# Power_systems_board_REV2.net
KiCad netlist of a schematic drawn in EAGLE
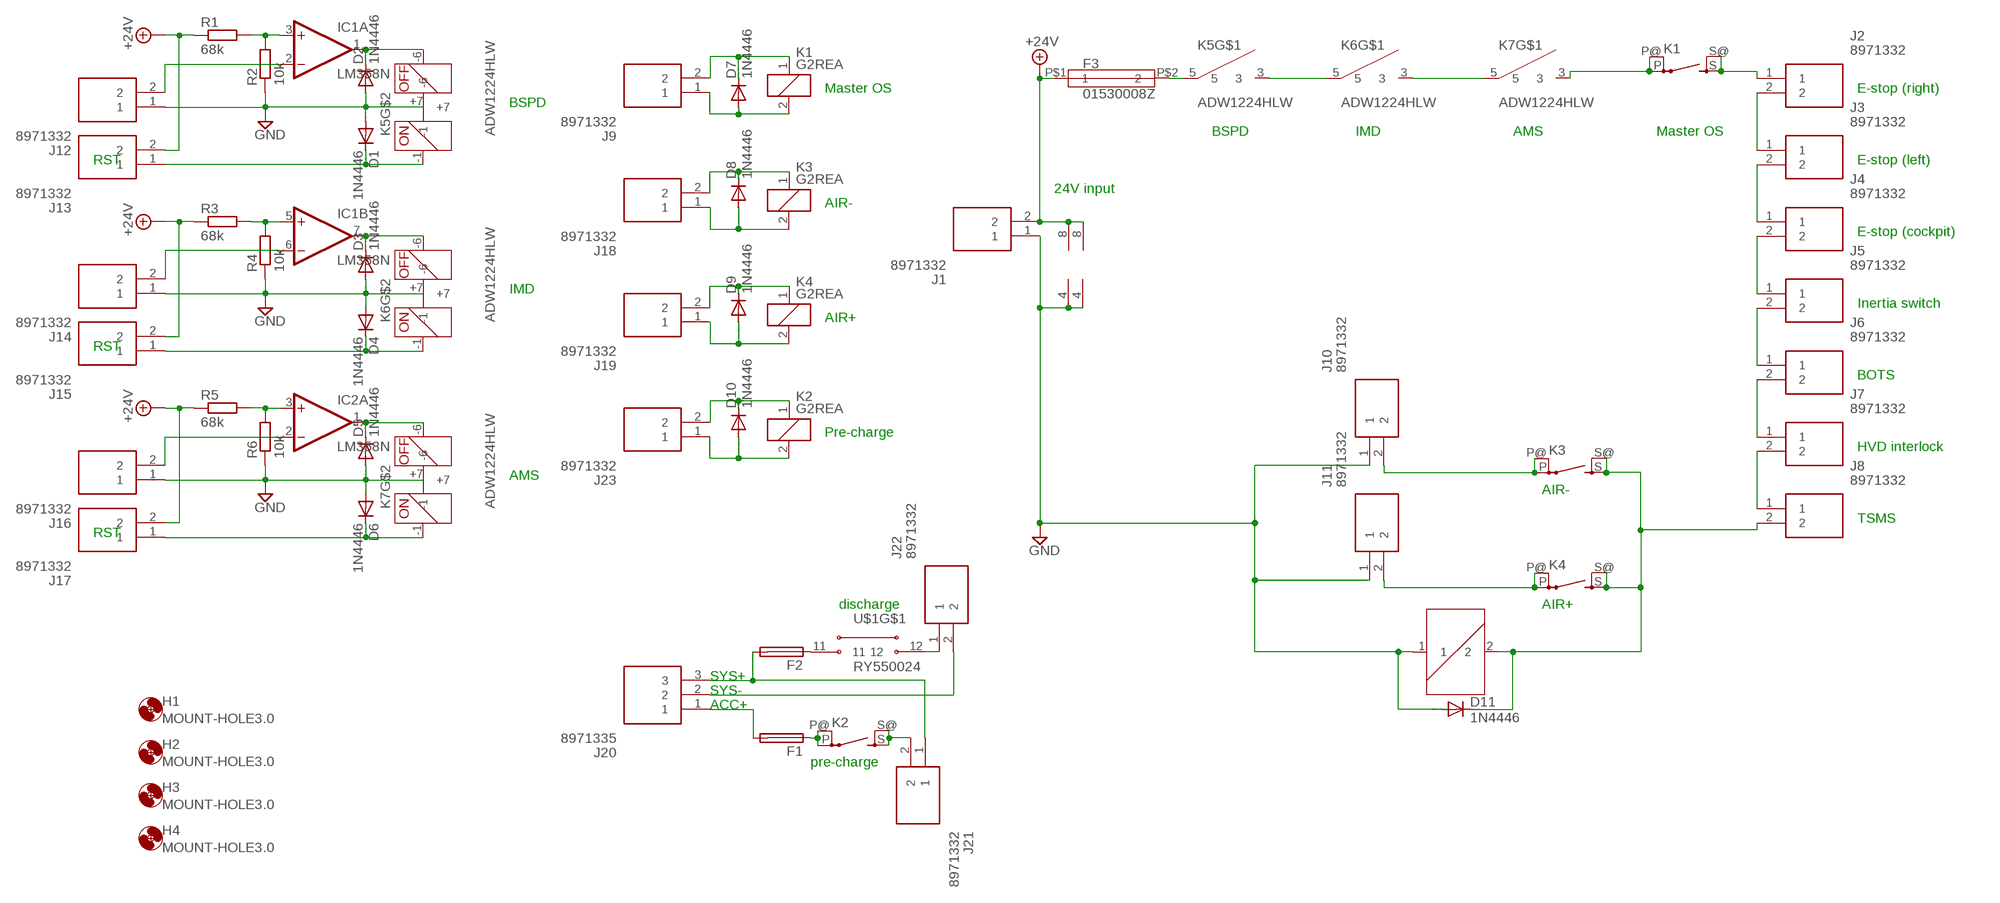
[diagram p0: schematic, sheet 1]

(export (version "E")
  (design (tool "Eeschema 10.0.6"))
  (components
    (comp (ref "D1")
      (value "1N4446")
      (footprint "eagle-import:DO35-10")
      (libsource (lib "eagle-import") (part "1N4446"))
    )
    (comp (ref "D2")
      (value "1N4446")
      (footprint "eagle-import:DO35-10")
      (libsource (lib "eagle-import") (part "1N4446"))
    )
    (comp (ref "D3")
      (value "1N4446")
      (footprint "eagle-import:DO35-10")
      (libsource (lib "eagle-import") (part "1N4446"))
    )
    (comp (ref "D4")
      (value "1N4446")
      (footprint "eagle-import:DO35-10")
      (libsource (lib "eagle-import") (part "1N4446"))
    )
    (comp (ref "D5")
      (value "1N4446")
      (footprint "eagle-import:DO35-10")
      (libsource (lib "eagle-import") (part "1N4446"))
    )
    (comp (ref "D6")
      (value "1N4446")
      (footprint "eagle-import:DO35-10")
      (libsource (lib "eagle-import") (part "1N4446"))
    )
    (comp (ref "D7")
      (value "1N4446")
      (footprint "eagle-import:DO35-10")
      (libsource (lib "eagle-import") (part "1N4446"))
    )
    (comp (ref "D8")
      (value "1N4446")
      (footprint "eagle-import:DO35-10")
      (libsource (lib "eagle-import") (part "1N4446"))
    )
    (comp (ref "D9")
      (value "1N4446")
      (footprint "eagle-import:DO35-10")
      (libsource (lib "eagle-import") (part "1N4446"))
    )
    (comp (ref "D10")
      (value "1N4446")
      (footprint "eagle-import:DO35-10")
      (libsource (lib "eagle-import") (part "1N4446"))
    )
    (comp (ref "D11")
      (value "1N4446")
      (footprint "eagle-import:DO35-10")
      (libsource (lib "eagle-import") (part "1N4446"))
    )
    (comp (ref "F1")
      (value "GSH15")
      (footprint "eagle-import:GSH15")
      (fields (field (name "MPN") "64900001039"))
      (libsource (lib "eagle-import") (part "GSH15"))
    )
    (comp (ref "F2")
      (value "GSH15")
      (footprint "eagle-import:GSH15")
      (fields (field (name "MPN") "64900001039"))
      (libsource (lib "eagle-import") (part "GSH15"))
    )
    (comp (ref "F3")
      (value "01530008Z")
      (footprint "eagle-import:01530008Z")
      (libsource (lib "eagle-import") (part "01530008Z"))
    )
    (comp (ref "H1")
      (value "MOUNT-HOLE3.0")
      (footprint "eagle-import:3,0")
      (libsource (lib "eagle-import") (part "MOUNT-HOLE3.0"))
    )
    (comp (ref "H2")
      (value "MOUNT-HOLE3.0")
      (footprint "eagle-import:3,0")
      (libsource (lib "eagle-import") (part "MOUNT-HOLE3.0"))
    )
    (comp (ref "H3")
      (value "MOUNT-HOLE3.0")
      (footprint "eagle-import:3,0")
      (libsource (lib "eagle-import") (part "MOUNT-HOLE3.0"))
    )
    (comp (ref "H4")
      (value "MOUNT-HOLE3.0")
      (footprint "eagle-import:3,0")
      (libsource (lib "eagle-import") (part "MOUNT-HOLE3.0"))
    )
    (comp (ref "IC1")
      (value "LM358N")
      (footprint "eagle-import:DIL08")
      (fields (field (name "SPICEPREFIX") "J"))
      (libsource (lib "eagle-import") (part "LM358N"))
    )
    (comp (ref "IC2")
      (value "LM358N")
      (footprint "eagle-import:DIL08")
      (libsource (lib "eagle-import") (part "LM358N"))
    )
    (comp (ref "J1")
      (value "8971332")
      (footprint "eagle-import:SHDR2W90P0X350_1X2_700X700X850")
      (libsource (lib "eagle-import") (part "8971332"))
    )
    (comp (ref "J2")
      (value "8971332")
      (footprint "eagle-import:SHDR2W90P0X350_1X2_700X700X850")
      (libsource (lib "eagle-import") (part "8971332"))
    )
    (comp (ref "J3")
      (value "8971332")
      (footprint "eagle-import:SHDR2W90P0X350_1X2_700X700X850")
      (libsource (lib "eagle-import") (part "8971332"))
    )
    (comp (ref "J4")
      (value "8971332")
      (footprint "eagle-import:SHDR2W90P0X350_1X2_700X700X850")
      (libsource (lib "eagle-import") (part "8971332"))
    )
    (comp (ref "J5")
      (value "8971332")
      (footprint "eagle-import:SHDR2W90P0X350_1X2_700X700X850")
      (libsource (lib "eagle-import") (part "8971332"))
    )
    (comp (ref "J6")
      (value "8971332")
      (footprint "eagle-import:SHDR2W90P0X350_1X2_700X700X850")
      (libsource (lib "eagle-import") (part "8971332"))
    )
    (comp (ref "J7")
      (value "8971332")
      (footprint "eagle-import:SHDR2W90P0X350_1X2_700X700X850")
      (libsource (lib "eagle-import") (part "8971332"))
    )
    (comp (ref "J8")
      (value "8971332")
      (footprint "eagle-import:SHDR2W90P0X350_1X2_700X700X850")
      (libsource (lib "eagle-import") (part "8971332"))
    )
    (comp (ref "J9")
      (value "8971332")
      (footprint "eagle-import:SHDR2W90P0X350_1X2_700X700X850")
      (libsource (lib "eagle-import") (part "8971332"))
    )
    (comp (ref "J10")
      (value "8971332")
      (footprint "eagle-import:SHDR2W90P0X350_1X2_700X700X850")
      (libsource (lib "eagle-import") (part "8971332"))
    )
    (comp (ref "J11")
      (value "8971332")
      (footprint "eagle-import:SHDR2W90P0X350_1X2_700X700X850")
      (libsource (lib "eagle-import") (part "8971332"))
    )
    (comp (ref "J12")
      (value "8971332")
      (footprint "eagle-import:SHDR2W90P0X350_1X2_700X700X850")
      (libsource (lib "eagle-import") (part "8971332"))
    )
    (comp (ref "J13")
      (value "8971332")
      (footprint "eagle-import:SHDR2W90P0X350_1X2_700X700X850")
      (libsource (lib "eagle-import") (part "8971332"))
    )
    (comp (ref "J14")
      (value "8971332")
      (footprint "eagle-import:SHDR2W90P0X350_1X2_700X700X850")
      (libsource (lib "eagle-import") (part "8971332"))
    )
    (comp (ref "J15")
      (value "8971332")
      (footprint "eagle-import:SHDR2W90P0X350_1X2_700X700X850")
      (libsource (lib "eagle-import") (part "8971332"))
    )
    (comp (ref "J16")
      (value "8971332")
      (footprint "eagle-import:SHDR2W90P0X350_1X2_700X700X850")
      (libsource (lib "eagle-import") (part "8971332"))
    )
    (comp (ref "J17")
      (value "8971332")
      (footprint "eagle-import:SHDR2W90P0X350_1X2_700X700X850")
      (libsource (lib "eagle-import") (part "8971332"))
    )
    (comp (ref "J18")
      (value "8971332")
      (footprint "eagle-import:SHDR2W90P0X350_1X2_700X700X850")
      (libsource (lib "eagle-import") (part "8971332"))
    )
    (comp (ref "J19")
      (value "8971332")
      (footprint "eagle-import:SHDR2W90P0X350_1X2_700X700X850")
      (libsource (lib "eagle-import") (part "8971332"))
    )
    (comp (ref "J20")
      (value "8971335")
      (footprint "eagle-import:SHDR3W90P0X350_1X3_1050X700X85")
      (libsource (lib "eagle-import") (part "8971335"))
    )
    (comp (ref "J21")
      (value "8971332")
      (footprint "eagle-import:SHDR2W90P0X350_1X2_700X700X850")
      (libsource (lib "eagle-import") (part "8971332"))
    )
    (comp (ref "J22")
      (value "8971332")
      (footprint "eagle-import:SHDR2W90P0X350_1X2_700X700X850")
      (libsource (lib "eagle-import") (part "8971332"))
    )
    (comp (ref "J23")
      (value "8971332")
      (footprint "eagle-import:SHDR2W90P0X350_1X2_700X700X850")
      (libsource (lib "eagle-import") (part "8971332"))
    )
    (comp (ref "K1")
      (value "G2REA")
      (footprint "eagle-import:G2REA")
      (libsource (lib "eagle-import") (part "G2REA"))
    )
    (comp (ref "K2")
      (value "G2REA")
      (footprint "eagle-import:G2REA")
      (libsource (lib "eagle-import") (part "G2REA"))
    )
    (comp (ref "K3")
      (value "G2REA")
      (footprint "eagle-import:G2REA")
      (libsource (lib "eagle-import") (part "G2REA"))
    )
    (comp (ref "K4")
      (value "G2REA")
      (footprint "eagle-import:G2REA")
      (libsource (lib "eagle-import") (part "G2REA"))
    )
    (comp (ref "K5")
      (value "ADW1224HLW")
      (footprint "eagle-import:ADW1224HLW")
      (libsource (lib "eagle-import") (part "ADW1224HLW"))
    )
    (comp (ref "K6")
      (value "ADW1224HLW")
      (footprint "eagle-import:ADW1224HLW")
      (libsource (lib "eagle-import") (part "ADW1224HLW"))
    )
    (comp (ref "K7")
      (value "ADW1224HLW")
      (footprint "eagle-import:ADW1224HLW")
      (libsource (lib "eagle-import") (part "ADW1224HLW"))
    )
    (comp (ref "R1")
      (value "68k")
      (footprint "eagle-import:0204_7")
      (libsource (lib "eagle-import") (part "R-EU_0204/7"))
    )
    (comp (ref "R2")
      (value "10k")
      (footprint "eagle-import:0204_7")
      (libsource (lib "eagle-import") (part "R-EU_0204/7"))
    )
    (comp (ref "R3")
      (value "68k")
      (footprint "eagle-import:0204_7")
      (libsource (lib "eagle-import") (part "R-EU_0204/7"))
    )
    (comp (ref "R4")
      (value "10k")
      (footprint "eagle-import:0204_7")
      (libsource (lib "eagle-import") (part "R-EU_0204/7"))
    )
    (comp (ref "R5")
      (value "68k")
      (footprint "eagle-import:0204_7")
      (libsource (lib "eagle-import") (part "R-EU_0204/7"))
    )
    (comp (ref "R6")
      (value "10k")
      (footprint "eagle-import:0204_7")
      (libsource (lib "eagle-import") (part "R-EU_0204/7"))
    )
    (comp (ref "U$1")
      (value "RY550024")
      (footprint "eagle-import:RY550024")
      (libsource (lib "eagle-import") (part "RY550024"))
    )
  )
  (nets
    (net (code "1") (name "+24V") (class "Default")
      (node (ref "F3") (pin "P$1") (pinfunction "1_P$1") (pintype "bidirectional"))
      (node (ref "IC1") (pin "8") (pinfunction "V+_8") (pintype "power_in"))
      (node (ref "IC2") (pin "8") (pinfunction "V+_8") (pintype "power_in"))
      (node (ref "J1") (pin "2") (pinfunction "2_2") (pintype "bidirectional"))
      (node (ref "J13") (pin "2") (pinfunction "2_2") (pintype "bidirectional"))
      (node (ref "J15") (pin "2") (pinfunction "2_2") (pintype "bidirectional"))
      (node (ref "J17") (pin "2") (pinfunction "2_2") (pintype "bidirectional"))
      (node (ref "R1") (pin "1") (pinfunction "1_1") (pintype "passive"))
      (node (ref "R3") (pin "1") (pinfunction "1_1") (pintype "passive"))
      (node (ref "R5") (pin "1") (pinfunction "1_1") (pintype "passive"))
    )
    (net (code "2") (name "GND") (class "Default")
      (node (ref "D1") (pin "A") (pinfunction "A_A") (pintype "passive"))
      (node (ref "D11") (pin "A") (pinfunction "A_A") (pintype "passive"))
      (node (ref "D2") (pin "A") (pinfunction "A_A") (pintype "passive"))
      (node (ref "D3") (pin "A") (pinfunction "A_A") (pintype "passive"))
      (node (ref "D4") (pin "A") (pinfunction "A_A") (pintype "passive"))
      (node (ref "D5") (pin "A") (pinfunction "A_A") (pintype "passive"))
      (node (ref "D6") (pin "A") (pinfunction "A_A") (pintype "passive"))
      (node (ref "IC1") (pin "4") (pinfunction "V-_4") (pintype "power_in"))
      (node (ref "IC2") (pin "4") (pinfunction "V-_4") (pintype "power_in"))
      (node (ref "J1") (pin "1") (pinfunction "1_1") (pintype "bidirectional"))
      (node (ref "J10") (pin "1") (pinfunction "1_1") (pintype "bidirectional"))
      (node (ref "J11") (pin "1") (pinfunction "1_1") (pintype "bidirectional"))
      (node (ref "J12") (pin "1") (pinfunction "1_1") (pintype "bidirectional"))
      (node (ref "J14") (pin "1") (pinfunction "1_1") (pintype "bidirectional"))
      (node (ref "J16") (pin "1") (pinfunction "1_1") (pintype "bidirectional"))
      (node (ref "K5") (pin "+7") (pinfunction "+7_+7") (pintype "bidirectional"))
      (node (ref "K6") (pin "+7") (pinfunction "+7_+7") (pintype "bidirectional"))
      (node (ref "K7") (pin "+7") (pinfunction "+7_+7") (pintype "bidirectional"))
      (node (ref "R2") (pin "1") (pinfunction "1_1") (pintype "passive"))
      (node (ref "R4") (pin "1") (pinfunction "1_1") (pintype "passive"))
      (node (ref "R6") (pin "1") (pinfunction "1_1") (pintype "passive"))
      (node (ref "U$1") (pin "1") (pinfunction "1_1") (pintype "bidirectional"))
    )
    (net (code "3") (name "Net-(D1-PadC)") (class "Default")
      (node (ref "D1") (pin "C") (pinfunction "C_C") (pintype "passive"))
      (node (ref "J13") (pin "1") (pinfunction "1_1") (pintype "bidirectional"))
      (node (ref "K5") (pin "-1") (pinfunction "-1_-1") (pintype "bidirectional"))
    )
    (net (code "4") (name "Net-(D4-PadC)") (class "Default")
      (node (ref "D4") (pin "C") (pinfunction "C_C") (pintype "passive"))
      (node (ref "J15") (pin "1") (pinfunction "1_1") (pintype "bidirectional"))
      (node (ref "K6") (pin "-1") (pinfunction "-1_-1") (pintype "bidirectional"))
    )
    (net (code "5") (name "Net-(D6-PadC)") (class "Default")
      (node (ref "D6") (pin "C") (pinfunction "C_C") (pintype "passive"))
      (node (ref "J17") (pin "1") (pinfunction "1_1") (pintype "bidirectional"))
      (node (ref "K7") (pin "-1") (pinfunction "-1_-1") (pintype "bidirectional"))
    )
    (net (code "6") (name "Net-(D7-PadA)") (class "Default")
      (node (ref "D7") (pin "A") (pinfunction "A_A") (pintype "passive"))
      (node (ref "J9") (pin "1") (pinfunction "1_1") (pintype "bidirectional"))
      (node (ref "K1") (pin "2") (pinfunction "2_2") (pintype "passive"))
    )
    (net (code "7") (name "Net-(D7-PadC)") (class "Default")
      (node (ref "D7") (pin "C") (pinfunction "C_C") (pintype "passive"))
      (node (ref "J9") (pin "2") (pinfunction "2_2") (pintype "bidirectional"))
      (node (ref "K1") (pin "1") (pinfunction "1_1") (pintype "passive"))
    )
    (net (code "8") (name "Net-(D8-PadA)") (class "Default")
      (node (ref "D8") (pin "A") (pinfunction "A_A") (pintype "passive"))
      (node (ref "J18") (pin "1") (pinfunction "1_1") (pintype "bidirectional"))
      (node (ref "K3") (pin "2") (pinfunction "2_2") (pintype "passive"))
    )
    (net (code "9") (name "Net-(D8-PadC)") (class "Default")
      (node (ref "D8") (pin "C") (pinfunction "C_C") (pintype "passive"))
      (node (ref "J18") (pin "2") (pinfunction "2_2") (pintype "bidirectional"))
      (node (ref "K3") (pin "1") (pinfunction "1_1") (pintype "passive"))
    )
    (net (code "10") (name "Net-(D9-PadA)") (class "Default")
      (node (ref "D9") (pin "A") (pinfunction "A_A") (pintype "passive"))
      (node (ref "J19") (pin "1") (pinfunction "1_1") (pintype "bidirectional"))
      (node (ref "K4") (pin "2") (pinfunction "2_2") (pintype "passive"))
    )
    (net (code "11") (name "Net-(D9-PadC)") (class "Default")
      (node (ref "D9") (pin "C") (pinfunction "C_C") (pintype "passive"))
      (node (ref "J19") (pin "2") (pinfunction "2_2") (pintype "bidirectional"))
      (node (ref "K4") (pin "1") (pinfunction "1_1") (pintype "passive"))
    )
    (net (code "12") (name "Net-(D10-PadA)") (class "Default")
      (node (ref "D10") (pin "A") (pinfunction "A_A") (pintype "passive"))
      (node (ref "J23") (pin "1") (pinfunction "1_1") (pintype "bidirectional"))
      (node (ref "K2") (pin "2") (pinfunction "2_2") (pintype "passive"))
    )
    (net (code "13") (name "Net-(D10-PadC)") (class "Default")
      (node (ref "D10") (pin "C") (pinfunction "C_C") (pintype "passive"))
      (node (ref "J23") (pin "2") (pinfunction "2_2") (pintype "bidirectional"))
      (node (ref "K2") (pin "1") (pinfunction "1_1") (pintype "passive"))
    )
    (net (code "14") (name "Net-(D11-PadC)") (class "Default")
      (node (ref "D11") (pin "C") (pinfunction "C_C") (pintype "passive"))
      (node (ref "J8") (pin "2") (pinfunction "2_2") (pintype "bidirectional"))
      (node (ref "K3") (pin "S") (pinfunction "S_S") (pintype "passive"))
      (node (ref "K3") (pin "S@") (pinfunction "S_S@") (pintype "passive"))
      (node (ref "K4") (pin "S") (pinfunction "S_S") (pintype "passive"))
      (node (ref "K4") (pin "S@") (pinfunction "S_S@") (pintype "passive"))
      (node (ref "U$1") (pin "2") (pinfunction "2_2") (pintype "bidirectional"))
    )
    (net (code "15") (name "Net-(F1-Pad1)") (class "Default")
      (node (ref "F1") (pin "1") (pinfunction "1_1") (pintype "passive"))
      (node (ref "K2") (pin "P") (pinfunction "P_P") (pintype "passive"))
      (node (ref "K2") (pin "P@") (pinfunction "P_P@") (pintype "passive"))
    )
    (net (code "16") (name "Net-(F1-Pad2)") (class "Default")
      (node (ref "F1") (pin "2") (pinfunction "2_2") (pintype "passive"))
      (node (ref "J20") (pin "1") (pinfunction "1_1") (pintype "bidirectional"))
    )
    (net (code "17") (name "Net-(F2-Pad1)") (class "Default")
      (node (ref "F2") (pin "1") (pinfunction "1_1") (pintype "passive"))
      (node (ref "U$1") (pin "11") (pinfunction "11_11") (pintype "bidirectional"))
    )
    (net (code "18") (name "Net-(F2-Pad2)") (class "Default")
      (node (ref "F2") (pin "2") (pinfunction "2_2") (pintype "passive"))
      (node (ref "J20") (pin "3") (pinfunction "3_3") (pintype "bidirectional"))
      (node (ref "J21") (pin "1") (pinfunction "1_1") (pintype "bidirectional"))
    )
    (net (code "19") (name "Net-(F3-2)") (class "Default")
      (node (ref "F3") (pin "P$2") (pinfunction "2_P$2") (pintype "bidirectional"))
      (node (ref "K5") (pin "5") (pinfunction "5_5") (pintype "bidirectional"))
    )
    (net (code "20") (name "Net-(IC1A-+IN)") (class "Default")
      (node (ref "IC1") (pin "3") (pinfunction "+IN_3") (pintype "input"))
      (node (ref "R1") (pin "2") (pinfunction "2_2") (pintype "passive"))
      (node (ref "R2") (pin "2") (pinfunction "2_2") (pintype "passive"))
    )
    (net (code "21") (name "Net-(IC1A--IN)") (class "Default")
      (node (ref "IC1") (pin "2") (pinfunction "-IN_2") (pintype "input"))
      (node (ref "J12") (pin "2") (pinfunction "2_2") (pintype "bidirectional"))
    )
    (net (code "22") (name "Net-(IC1A-OUT)") (class "Default")
      (node (ref "D2") (pin "C") (pinfunction "C_C") (pintype "passive"))
      (node (ref "IC1") (pin "1") (pinfunction "OUT_1") (pintype "output"))
      (node (ref "K5") (pin "-6") (pinfunction "-6_-6") (pintype "bidirectional"))
    )
    (net (code "23") (name "Net-(IC1B-+IN)") (class "Default")
      (node (ref "IC1") (pin "5") (pinfunction "+IN_5") (pintype "input"))
      (node (ref "R3") (pin "2") (pinfunction "2_2") (pintype "passive"))
      (node (ref "R4") (pin "2") (pinfunction "2_2") (pintype "passive"))
    )
    (net (code "24") (name "Net-(IC1B--IN)") (class "Default")
      (node (ref "IC1") (pin "6") (pinfunction "-IN_6") (pintype "input"))
      (node (ref "J14") (pin "2") (pinfunction "2_2") (pintype "bidirectional"))
    )
    (net (code "25") (name "Net-(IC1B-OUT)") (class "Default")
      (node (ref "D3") (pin "C") (pinfunction "C_C") (pintype "passive"))
      (node (ref "IC1") (pin "7") (pinfunction "OUT_7") (pintype "output"))
      (node (ref "K6") (pin "-6") (pinfunction "-6_-6") (pintype "bidirectional"))
    )
    (net (code "26") (name "Net-(IC2A-+IN)") (class "Default")
      (node (ref "IC2") (pin "3") (pinfunction "+IN_3") (pintype "input"))
      (node (ref "R5") (pin "2") (pinfunction "2_2") (pintype "passive"))
      (node (ref "R6") (pin "2") (pinfunction "2_2") (pintype "passive"))
    )
    (net (code "27") (name "Net-(IC2A--IN)") (class "Default")
      (node (ref "IC2") (pin "2") (pinfunction "-IN_2") (pintype "input"))
      (node (ref "J16") (pin "2") (pinfunction "2_2") (pintype "bidirectional"))
    )
    (net (code "28") (name "Net-(IC2A-OUT)") (class "Default")
      (node (ref "D5") (pin "C") (pinfunction "C_C") (pintype "passive"))
      (node (ref "IC2") (pin "1") (pinfunction "OUT_1") (pintype "output"))
      (node (ref "K7") (pin "-6") (pinfunction "-6_-6") (pintype "bidirectional"))
    )
    (net (code "29") (name "Net-(J2-Pad1)") (class "Default")
      (node (ref "J2") (pin "1") (pinfunction "1_1") (pintype "bidirectional"))
      (node (ref "K1") (pin "S") (pinfunction "S_S") (pintype "passive"))
      (node (ref "K1") (pin "S@") (pinfunction "S_S@") (pintype "passive"))
    )
    (net (code "30") (name "Net-(J2-Pad2)") (class "Default")
      (node (ref "J2") (pin "2") (pinfunction "2_2") (pintype "bidirectional"))
      (node (ref "J3") (pin "1") (pinfunction "1_1") (pintype "bidirectional"))
    )
    (net (code "31") (name "Net-(J3-Pad2)") (class "Default")
      (node (ref "J3") (pin "2") (pinfunction "2_2") (pintype "bidirectional"))
      (node (ref "J4") (pin "1") (pinfunction "1_1") (pintype "bidirectional"))
    )
    (net (code "32") (name "Net-(J4-Pad2)") (class "Default")
      (node (ref "J4") (pin "2") (pinfunction "2_2") (pintype "bidirectional"))
      (node (ref "J5") (pin "1") (pinfunction "1_1") (pintype "bidirectional"))
    )
    (net (code "33") (name "Net-(J5-Pad2)") (class "Default")
      (node (ref "J5") (pin "2") (pinfunction "2_2") (pintype "bidirectional"))
      (node (ref "J6") (pin "1") (pinfunction "1_1") (pintype "bidirectional"))
    )
    (net (code "34") (name "Net-(J6-Pad2)") (class "Default")
      (node (ref "J6") (pin "2") (pinfunction "2_2") (pintype "bidirectional"))
      (node (ref "J7") (pin "1") (pinfunction "1_1") (pintype "bidirectional"))
    )
    (net (code "35") (name "Net-(J7-Pad2)") (class "Default")
      (node (ref "J7") (pin "2") (pinfunction "2_2") (pintype "bidirectional"))
      (node (ref "J8") (pin "1") (pinfunction "1_1") (pintype "bidirectional"))
    )
    (net (code "36") (name "Net-(J10-Pad2)") (class "Default")
      (node (ref "J10") (pin "2") (pinfunction "2_2") (pintype "bidirectional"))
      (node (ref "K3") (pin "P") (pinfunction "P_P") (pintype "passive"))
      (node (ref "K3") (pin "P@") (pinfunction "P_P@") (pintype "passive"))
    )
    (net (code "37") (name "Net-(J11-Pad2)") (class "Default")
      (node (ref "J11") (pin "2") (pinfunction "2_2") (pintype "bidirectional"))
      (node (ref "K4") (pin "P") (pinfunction "P_P") (pintype "passive"))
      (node (ref "K4") (pin "P@") (pinfunction "P_P@") (pintype "passive"))
    )
    (net (code "38") (name "Net-(J20-Pad2)") (class "Default")
      (node (ref "J20") (pin "2") (pinfunction "2_2") (pintype "bidirectional"))
      (node (ref "J22") (pin "2") (pinfunction "2_2") (pintype "bidirectional"))
    )
    (net (code "39") (name "Net-(J21-Pad2)") (class "Default")
      (node (ref "J21") (pin "2") (pinfunction "2_2") (pintype "bidirectional"))
      (node (ref "K2") (pin "S") (pinfunction "S_S") (pintype "passive"))
      (node (ref "K2") (pin "S@") (pinfunction "S_S@") (pintype "passive"))
    )
    (net (code "40") (name "Net-(J22-Pad1)") (class "Default")
      (node (ref "J22") (pin "1") (pinfunction "1_1") (pintype "bidirectional"))
      (node (ref "U$1") (pin "12") (pinfunction "12_12") (pintype "bidirectional"))
    )
    (net (code "41") (name "Net-(K1-PadP)") (class "Default")
      (node (ref "K1") (pin "P") (pinfunction "P_P") (pintype "passive"))
      (node (ref "K1") (pin "P@") (pinfunction "P_P@") (pintype "passive"))
      (node (ref "K7") (pin "3") (pinfunction "3_3") (pintype "bidirectional"))
    )
    (net (code "42") (name "Net-(K5-Pad3)") (class "Default")
      (node (ref "K5") (pin "3") (pinfunction "3_3") (pintype "bidirectional"))
      (node (ref "K6") (pin "5") (pinfunction "5_5") (pintype "bidirectional"))
    )
    (net (code "43") (name "Net-(K6-Pad3)") (class "Default")
      (node (ref "K6") (pin "3") (pinfunction "3_3") (pintype "bidirectional"))
      (node (ref "K7") (pin "5") (pinfunction "5_5") (pintype "bidirectional"))
    )
  )
)
